# MDQARM_SOUND.net
KiCad netlist of a schematic drawn in Altium Designer
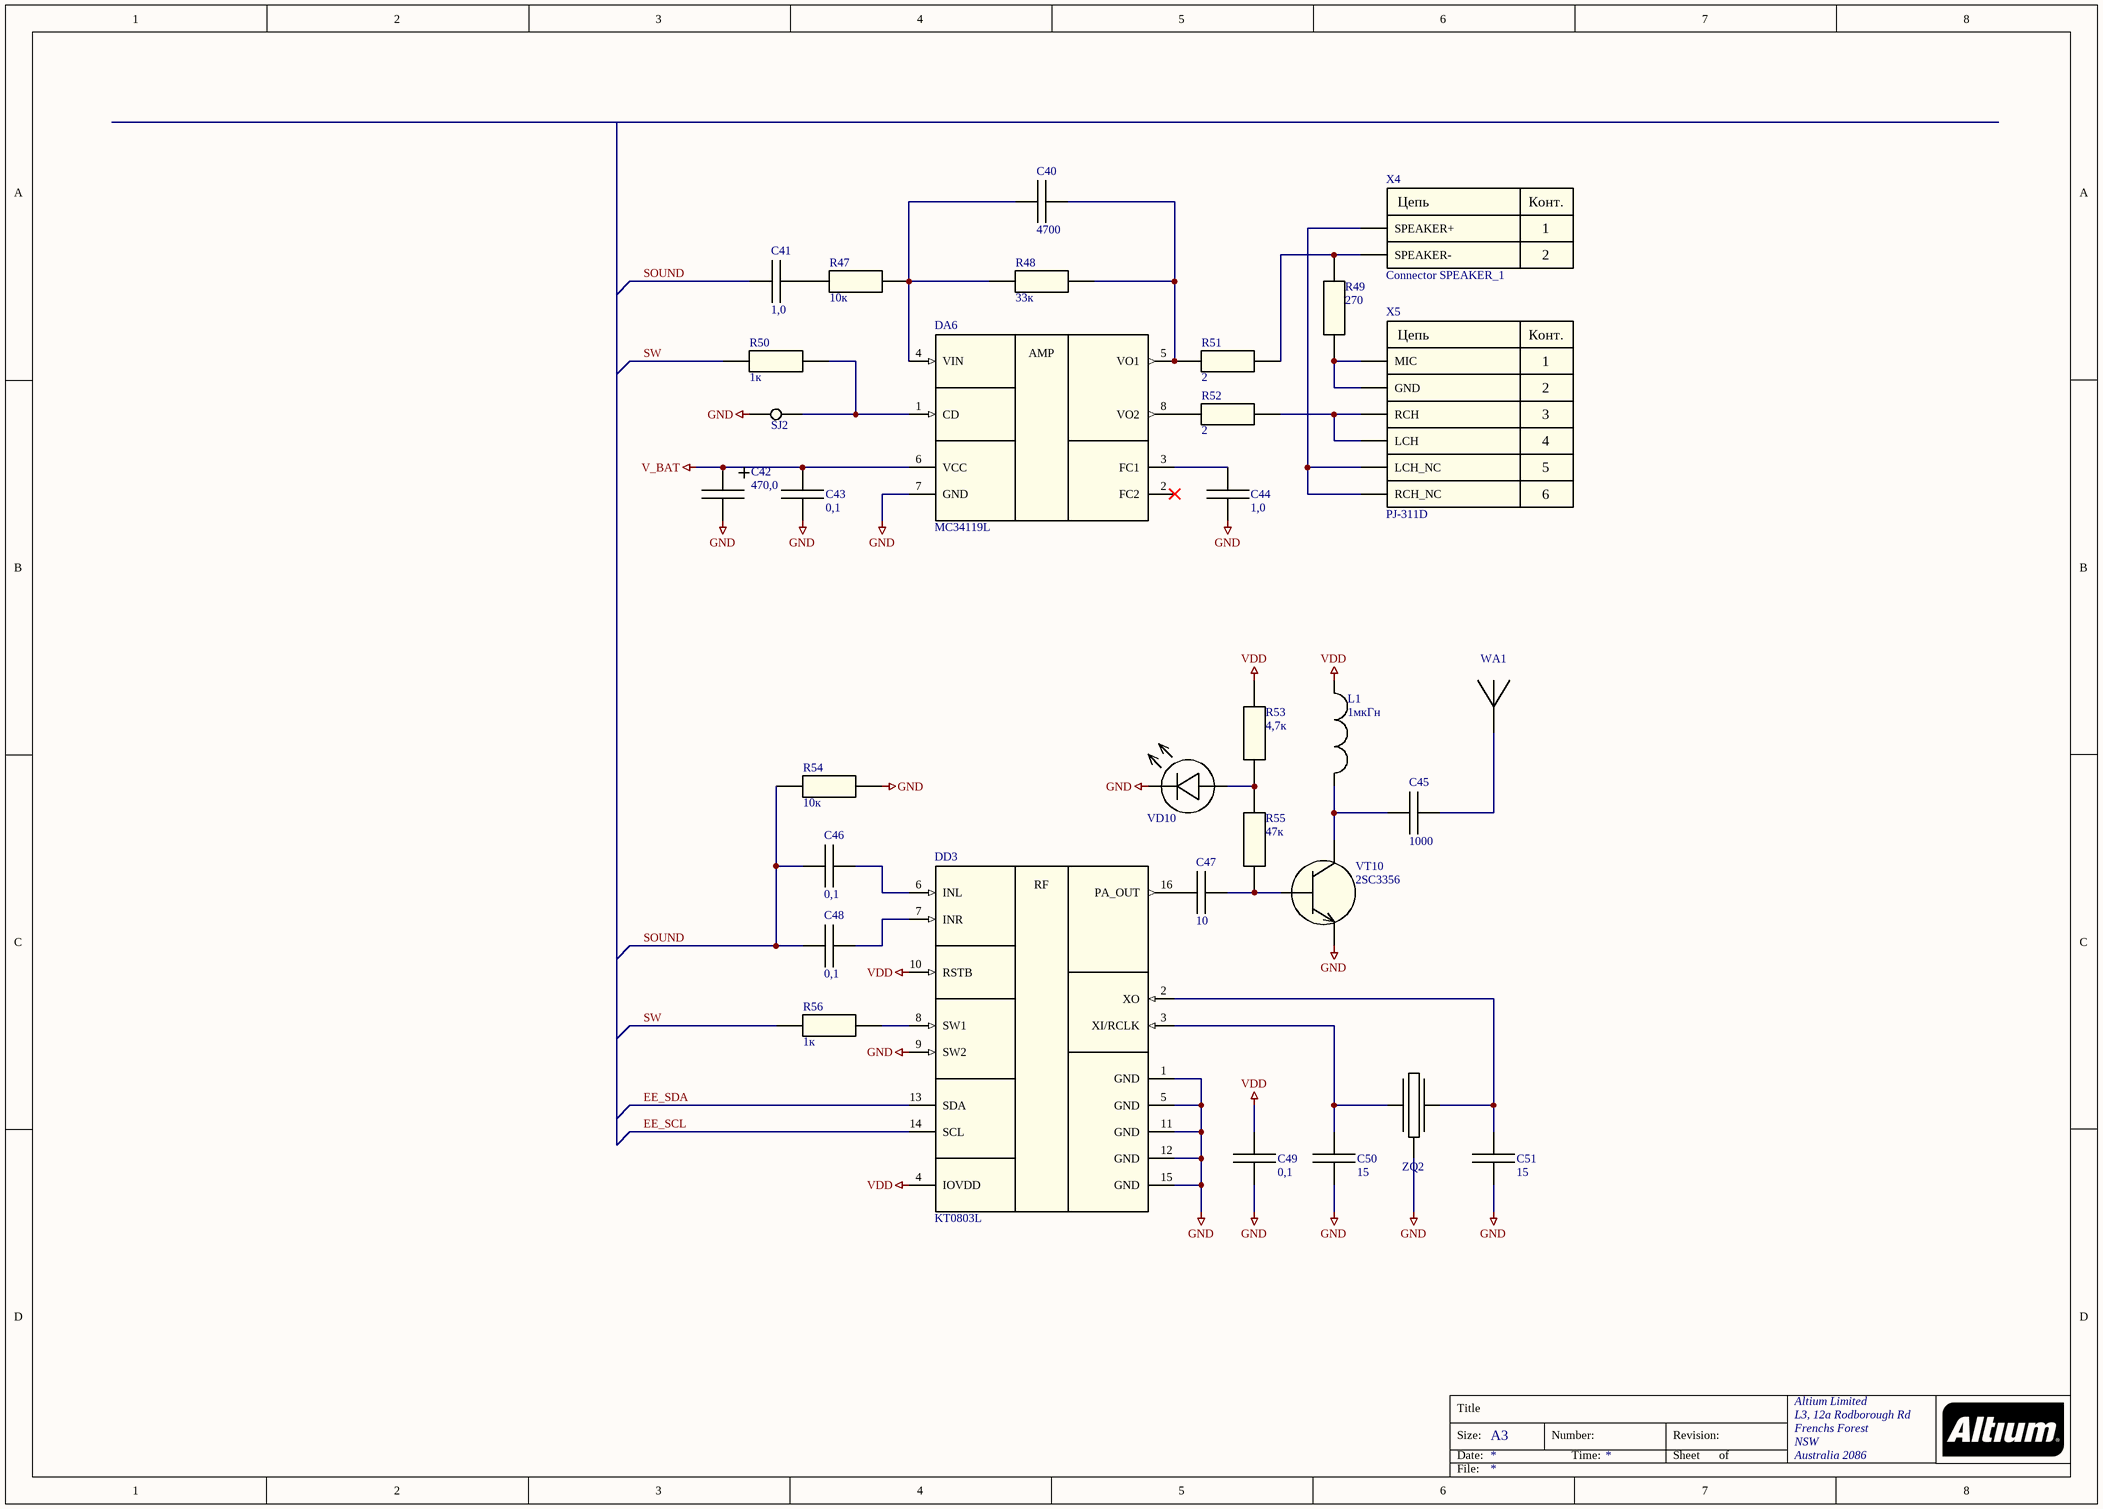
[diagram p0: MDQARM_SOUND.SchDoc]

(export (version "E")
  (design (tool "Eeschema 10.0.6"))
  (components
    (comp (ref "C40")
      (value "4700")
      (footprint "Capacitor SMD0805-T0.75")
      (libsource (lib "IVV_Passive") (part "Capacitor C0805_4.7n"))
    )
    (comp (ref "C41")
      (value "1,0")
      (footprint "Capacitor SMD0805-T1.35")
      (libsource (lib "IVV_Passive") (part "Capacitor C0805_1u"))
    )
    (comp (ref "C42")
      (value "470,0")
      (footprint "Capacitor ECAP SMD10x10.5")
      (libsource (lib "IVV_Passive") (part "Capacitor ECAP SMD 470uF_16V"))
    )
    (comp (ref "C43")
      (value "0,1")
      (footprint "Capacitor SMD0805-T0.95")
      (libsource (lib "IVV_Passive") (part "Capacitor C0805_100n"))
    )
    (comp (ref "C44")
      (value "1,0")
      (footprint "Capacitor SMD0805-T1.35")
      (libsource (lib "IVV_Passive") (part "Capacitor C0805_1u"))
    )
    (comp (ref "C45")
      (value "1000")
      (footprint "Capacitor SMD0805-T0.75")
      (libsource (lib "IVV_Passive") (part "Capacitor C0805_1n"))
    )
    (comp (ref "C46")
      (value "0,1")
      (footprint "Capacitor SMD0805-T0.95")
      (libsource (lib "IVV_Passive") (part "Capacitor C0805_100n"))
    )
    (comp (ref "C47")
      (value "10")
      (footprint "Capacitor SMD0805-T0.75")
      (libsource (lib "IVV_Passive") (part "Capacitor C0805_10p"))
    )
    (comp (ref "C48")
      (value "0,1")
      (footprint "Capacitor SMD0805-T0.95")
      (libsource (lib "IVV_Passive") (part "Capacitor C0805_100n"))
    )
    (comp (ref "C49")
      (value "0,1")
      (footprint "Capacitor SMD0805-T0.95")
      (libsource (lib "IVV_Passive") (part "Capacitor C0805_100n"))
    )
    (comp (ref "C50")
      (value "15")
      (footprint "Capacitor SMD0805-T0.75")
      (libsource (lib "IVV_Passive") (part "Capacitor C0805_15p"))
    )
    (comp (ref "C51")
      (value "15")
      (footprint "Capacitor SMD0805-T0.75")
      (libsource (lib "IVV_Passive") (part "Capacitor C0805_15p"))
    )
    (comp (ref "DA6")
      (value "MC34119L")
      (footprint "IC MC34119L")
      (libsource (lib "IVV_IC") (part "IC MC34119L"))
    )
    (comp (ref "DD3")
      (value "KT0803L")
      (footprint "IC KT0803L")
      (libsource (lib "IVV_IC") (part "IC KT0803L"))
    )
    (comp (ref "L1")
      (value "1мкГн")
      (footprint "Inductor SMD1210")
      (libsource (lib "IVV_Passive") (part "Inductance L1210_1uH"))
    )
    (comp (ref "R47")
      (value "10к")
      (footprint "Resistor SMD0805")
      (libsource (lib "IVV_Passive") (part "Resistor R0805_10k_5%"))
    )
    (comp (ref "R48")
      (value "33к")
      (footprint "Resistor SMD0805")
      (libsource (lib "IVV_Passive") (part "Resistor R0805_33k_5%"))
    )
    (comp (ref "R49")
      (value "270")
      (footprint "Resistor SMD0805")
      (libsource (lib "IVV_Passive") (part "Resistor R0805_270R_5%"))
    )
    (comp (ref "R50")
      (value "1к")
      (footprint "Resistor SMD0805")
      (libsource (lib "IVV_Passive") (part "Resistor R0805_1k_5%"))
    )
    (comp (ref "R51")
      (value "2")
      (footprint "Resistor SMD0805")
      (libsource (lib "IVV_Passive") (part "Resistor R0805_2R_5%"))
    )
    (comp (ref "R52")
      (value "2")
      (footprint "Resistor SMD0805")
      (libsource (lib "IVV_Passive") (part "Resistor R0805_2R_5%"))
    )
    (comp (ref "R53")
      (value "4,7к")
      (footprint "Resistor SMD0805")
      (libsource (lib "IVV_Passive") (part "Resistor R0805_4.7k_5%"))
    )
    (comp (ref "R54")
      (value "10к")
      (footprint "Resistor SMD0805")
      (libsource (lib "IVV_Passive") (part "Resistor R0805_10k_5%"))
    )
    (comp (ref "R55")
      (value "47к")
      (footprint "Resistor SMD0805")
      (libsource (lib "IVV_Passive") (part "Resistor R0805_47k_5%"))
    )
    (comp (ref "R56")
      (value "1к")
      (footprint "Resistor SMD0805")
      (libsource (lib "IVV_Passive") (part "Resistor R0805_1k_5%"))
    )
    (comp (ref "SJ2")
      (value "SolderJump 1")
      (footprint "SolderJump 1")
      (libsource (lib "IVV_Lib") (part "SolderJump 1"))
    )
    (comp (ref "VD10")
      (value "RED")
      (footprint "Diode SMD0805")
      (description "LED Red SMD0805")
      (libsource (lib "IVV_Lib") (part "Diode LED0805RED"))
    )
    (comp (ref "VT10")
      (value "2SC3356")
      (footprint "Transistor SOT23")
      (libsource (lib "IVV_Lib") (part "Transistor 2SC3356"))
    )
    (comp (ref "WA1")
      (value "Antenna 1")
      (footprint "Antenna 1")
      (libsource (lib "IVV_Lib") (part "Antenna 1"))
    )
    (comp (ref "X4")
      (value "Connector SPEAKER_1")
      (footprint "Connector SPEAKER")
      (libsource (lib "IVV_Connectors") (part "Connector SPEAKER_1"))
    )
    (comp (ref "X5")
      (value "PJ-311D")
      (footprint "Connector PJ-311D")
      (description "Audio Jack 3.5mm")
      (libsource (lib "IVV_Connectors") (part "Connector PJ-311D"))
    )
    (comp (ref "ZQ2")
      (value "32768 Гц")
      (footprint "Quartz DT-38T-32768Hz")
      (libsource (lib "IVV_Lib") (part "Quartz DT-38T-32768Hz"))
    )
  )
  (nets
    (net (code "1") (name "/EE_SCL") (class "Default")
      (node (ref "DD3") (pin "14") (pinfunction "SCL_14") (pintype "open_collector"))
    )
    (net (code "2") (name "/EE_SDA") (class "Default")
      (node (ref "DD3") (pin "13") (pinfunction "SDA_13") (pintype "open_collector"))
    )
    (net (code "3") (name "/SOUND") (class "Default")
      (node (ref "C41") (pin "1") (pinfunction "1_1") (pintype "passive"))
      (node (ref "C46") (pin "1") (pinfunction "1_1") (pintype "passive"))
      (node (ref "C48") (pin "1") (pinfunction "1_1") (pintype "passive"))
      (node (ref "R54") (pin "1") (pinfunction "1_1") (pintype "passive"))
    )
    (net (code "4") (name "/SW") (class "Default")
      (node (ref "R50") (pin "1") (pinfunction "1_1") (pintype "passive"))
      (node (ref "R56") (pin "1") (pinfunction "1_1") (pintype "passive"))
    )
    (net (code "5") (name "GND") (class "Default")
      (node (ref "C42") (pin "2") (pinfunction "2_2") (pintype "passive"))
      (node (ref "C43") (pin "1") (pinfunction "1_1") (pintype "passive"))
      (node (ref "C44") (pin "1") (pinfunction "1_1") (pintype "passive"))
      (node (ref "C49") (pin "1") (pinfunction "1_1") (pintype "passive"))
      (node (ref "C50") (pin "2") (pinfunction "2_2") (pintype "passive"))
      (node (ref "C51") (pin "2") (pinfunction "2_2") (pintype "passive"))
      (node (ref "DA6") (pin "7") (pinfunction "GND_7") (pintype "power_in"))
      (node (ref "DD3") (pin "1") (pinfunction "GND_1") (pintype "power_in"))
      (node (ref "DD3") (pin "11") (pinfunction "GND_11") (pintype "power_in"))
      (node (ref "DD3") (pin "12") (pinfunction "GND_12") (pintype "power_in"))
      (node (ref "DD3") (pin "15") (pinfunction "GND_15") (pintype "power_in"))
      (node (ref "DD3") (pin "5") (pinfunction "GND_5") (pintype "power_in"))
      (node (ref "DD3") (pin "9") (pinfunction "SW2_9") (pintype "input"))
      (node (ref "R54") (pin "2") (pinfunction "2_2") (pintype "passive"))
      (node (ref "SJ2") (pin "2") (pinfunction "2_2") (pintype "passive"))
      (node (ref "VD10") (pin "2") (pinfunction "C_2") (pintype "passive"))
      (node (ref "VT10") (pin "2") (pinfunction "E_2") (pintype "passive"))
      (node (ref "ZQ2") (pin "3") (pinfunction "GND_3") (pintype "power_in"))
    )
    (net (code "6") (name "Net-(C41-Pad2)") (class "Default")
      (node (ref "C41") (pin "2") (pinfunction "2_2") (pintype "passive"))
      (node (ref "R47") (pin "1") (pinfunction "1_1") (pintype "passive"))
    )
    (net (code "7") (name "Net-(C45-Pad2)") (class "Default")
      (node (ref "C45") (pin "2") (pinfunction "2_2") (pintype "passive"))
      (node (ref "WA1") (pin "1") (pinfunction "1_1") (pintype "passive"))
    )
    (net (code "8") (name "Net-(DA6-CD)") (class "Default")
      (node (ref "DA6") (pin "1") (pinfunction "CD_1") (pintype "input"))
      (node (ref "R50") (pin "2") (pinfunction "2_2") (pintype "passive"))
      (node (ref "SJ2") (pin "1") (pinfunction "1_1") (pintype "passive"))
    )
    (net (code "9") (name "Net-(DA6-FC1)") (class "Default")
      (node (ref "C44") (pin "2") (pinfunction "2_2") (pintype "passive"))
      (node (ref "DA6") (pin "3") (pinfunction "FC1_3") (pintype "passive"))
    )
    (net (code "10") (name "Net-(DA6-VIN)") (class "Default")
      (node (ref "C40") (pin "1") (pinfunction "1_1") (pintype "passive"))
      (node (ref "DA6") (pin "4") (pinfunction "VIN_4") (pintype "input"))
      (node (ref "R47") (pin "2") (pinfunction "2_2") (pintype "passive"))
      (node (ref "R48") (pin "1") (pinfunction "1_1") (pintype "passive"))
    )
    (net (code "11") (name "Net-(DA6-VO1)") (class "Default")
      (node (ref "C40") (pin "2") (pinfunction "2_2") (pintype "passive"))
      (node (ref "DA6") (pin "5") (pinfunction "VO1_5") (pintype "output"))
      (node (ref "R48") (pin "2") (pinfunction "2_2") (pintype "passive"))
      (node (ref "R51") (pin "1") (pinfunction "1_1") (pintype "passive"))
    )
    (net (code "12") (name "Net-(DA6-VO2)") (class "Default")
      (node (ref "DA6") (pin "8") (pinfunction "VO2_8") (pintype "output"))
      (node (ref "R52") (pin "1") (pinfunction "1_1") (pintype "passive"))
    )
    (net (code "13") (name "Net-(DD3-INL)") (class "Default")
      (node (ref "C46") (pin "2") (pinfunction "2_2") (pintype "passive"))
      (node (ref "DD3") (pin "6") (pinfunction "INL_6") (pintype "input"))
    )
    (net (code "14") (name "Net-(DD3-INR)") (class "Default")
      (node (ref "C48") (pin "2") (pinfunction "2_2") (pintype "passive"))
      (node (ref "DD3") (pin "7") (pinfunction "INR_7") (pintype "input"))
    )
    (net (code "15") (name "Net-(DD3-PA_OUT)") (class "Default")
      (node (ref "C47") (pin "1") (pinfunction "1_1") (pintype "passive"))
      (node (ref "DD3") (pin "16") (pinfunction "PA_OUT_16") (pintype "output"))
    )
    (net (code "16") (name "Net-(DD3-SW1)") (class "Default")
      (node (ref "DD3") (pin "8") (pinfunction "SW1_8") (pintype "input"))
      (node (ref "R56") (pin "2") (pinfunction "2_2") (pintype "passive"))
    )
    (net (code "17") (name "Net-(DD3-XI{slash}RCLK)") (class "Default")
      (node (ref "C50") (pin "1") (pinfunction "1_1") (pintype "passive"))
      (node (ref "DD3") (pin "3") (pinfunction "XI/RCLK_3") (pintype "input"))
      (node (ref "ZQ2") (pin "1") (pinfunction "1_1") (pintype "passive"))
    )
    (net (code "18") (name "Net-(DD3-XO)") (class "Default")
      (node (ref "C51") (pin "1") (pinfunction "1_1") (pintype "passive"))
      (node (ref "DD3") (pin "2") (pinfunction "XO_2") (pintype "input"))
      (node (ref "ZQ2") (pin "2") (pinfunction "2_2") (pintype "passive"))
    )
    (net (code "19") (name "Net-(VD10-A)") (class "Default")
      (node (ref "R53") (pin "2") (pinfunction "2_2") (pintype "passive"))
      (node (ref "R55") (pin "2") (pinfunction "2_2") (pintype "passive"))
      (node (ref "VD10") (pin "1") (pinfunction "A_1") (pintype "passive"))
    )
    (net (code "20") (name "Net-(VT10-B)") (class "Default")
      (node (ref "C47") (pin "2") (pinfunction "2_2") (pintype "passive"))
      (node (ref "R55") (pin "1") (pinfunction "1_1") (pintype "passive"))
      (node (ref "VT10") (pin "1") (pinfunction "B_1") (pintype "passive"))
    )
    (net (code "21") (name "Net-(VT10-C)") (class "Default")
      (node (ref "C45") (pin "1") (pinfunction "1_1") (pintype "passive"))
      (node (ref "L1") (pin "2") (pinfunction "2_2") (pintype "passive"))
      (node (ref "VT10") (pin "3") (pinfunction "C_3") (pintype "passive"))
    )
    (net (code "22") (name "Net-(X4-SPEAKER+)") (class "Default")
      (node (ref "X4") (pin "1") (pinfunction "SPEAKER+_1") (pintype "passive"))
      (node (ref "X5") (pin "5") (pinfunction "LCH_NC_5") (pintype "passive"))
      (node (ref "X5") (pin "6") (pinfunction "RCH_NC_6") (pintype "passive"))
    )
    (net (code "23") (name "Net-(X4-SPEAKER-)") (class "Default")
      (node (ref "R49") (pin "2") (pinfunction "2_2") (pintype "passive"))
      (node (ref "R51") (pin "2") (pinfunction "2_2") (pintype "passive"))
      (node (ref "X4") (pin "2") (pinfunction "SPEAKER-_2") (pintype "passive"))
    )
    (net (code "24") (name "Net-(X5-GND)") (class "Default")
      (node (ref "R49") (pin "1") (pinfunction "1_1") (pintype "passive"))
      (node (ref "X5") (pin "1") (pinfunction "MIC_1") (pintype "passive"))
      (node (ref "X5") (pin "2") (pinfunction "GND_2") (pintype "passive"))
    )
    (net (code "25") (name "Net-(X5-LCH)") (class "Default")
      (node (ref "R52") (pin "2") (pinfunction "2_2") (pintype "passive"))
      (node (ref "X5") (pin "3") (pinfunction "RCH_3") (pintype "passive"))
      (node (ref "X5") (pin "4") (pinfunction "LCH_4") (pintype "passive"))
    )
    (net (code "26") (name "VDD") (class "Default")
      (node (ref "C49") (pin "2") (pinfunction "2_2") (pintype "passive"))
      (node (ref "DD3") (pin "10") (pinfunction "RSTB_10") (pintype "input"))
      (node (ref "DD3") (pin "4") (pinfunction "IOVDD_4") (pintype "power_in"))
      (node (ref "L1") (pin "1") (pinfunction "1_1") (pintype "passive"))
      (node (ref "R53") (pin "1") (pinfunction "1_1") (pintype "passive"))
    )
    (net (code "27") (name "V_BAT") (class "Default")
      (node (ref "C42") (pin "1") (pinfunction "1_1") (pintype "passive"))
      (node (ref "C43") (pin "2") (pinfunction "2_2") (pintype "passive"))
      (node (ref "DA6") (pin "6") (pinfunction "VCC_6") (pintype "power_in"))
    )
    (net (code "28") (name "unconnected-(DA6-FC2-Pad2)") (class "Default")
      (node (ref "DA6") (pin "2") (pinfunction "FC2_2") (pintype "passive+no_connect"))
    )
  )
)
